# MCU.net
KiCad netlist of a schematic drawn in Altium Designer
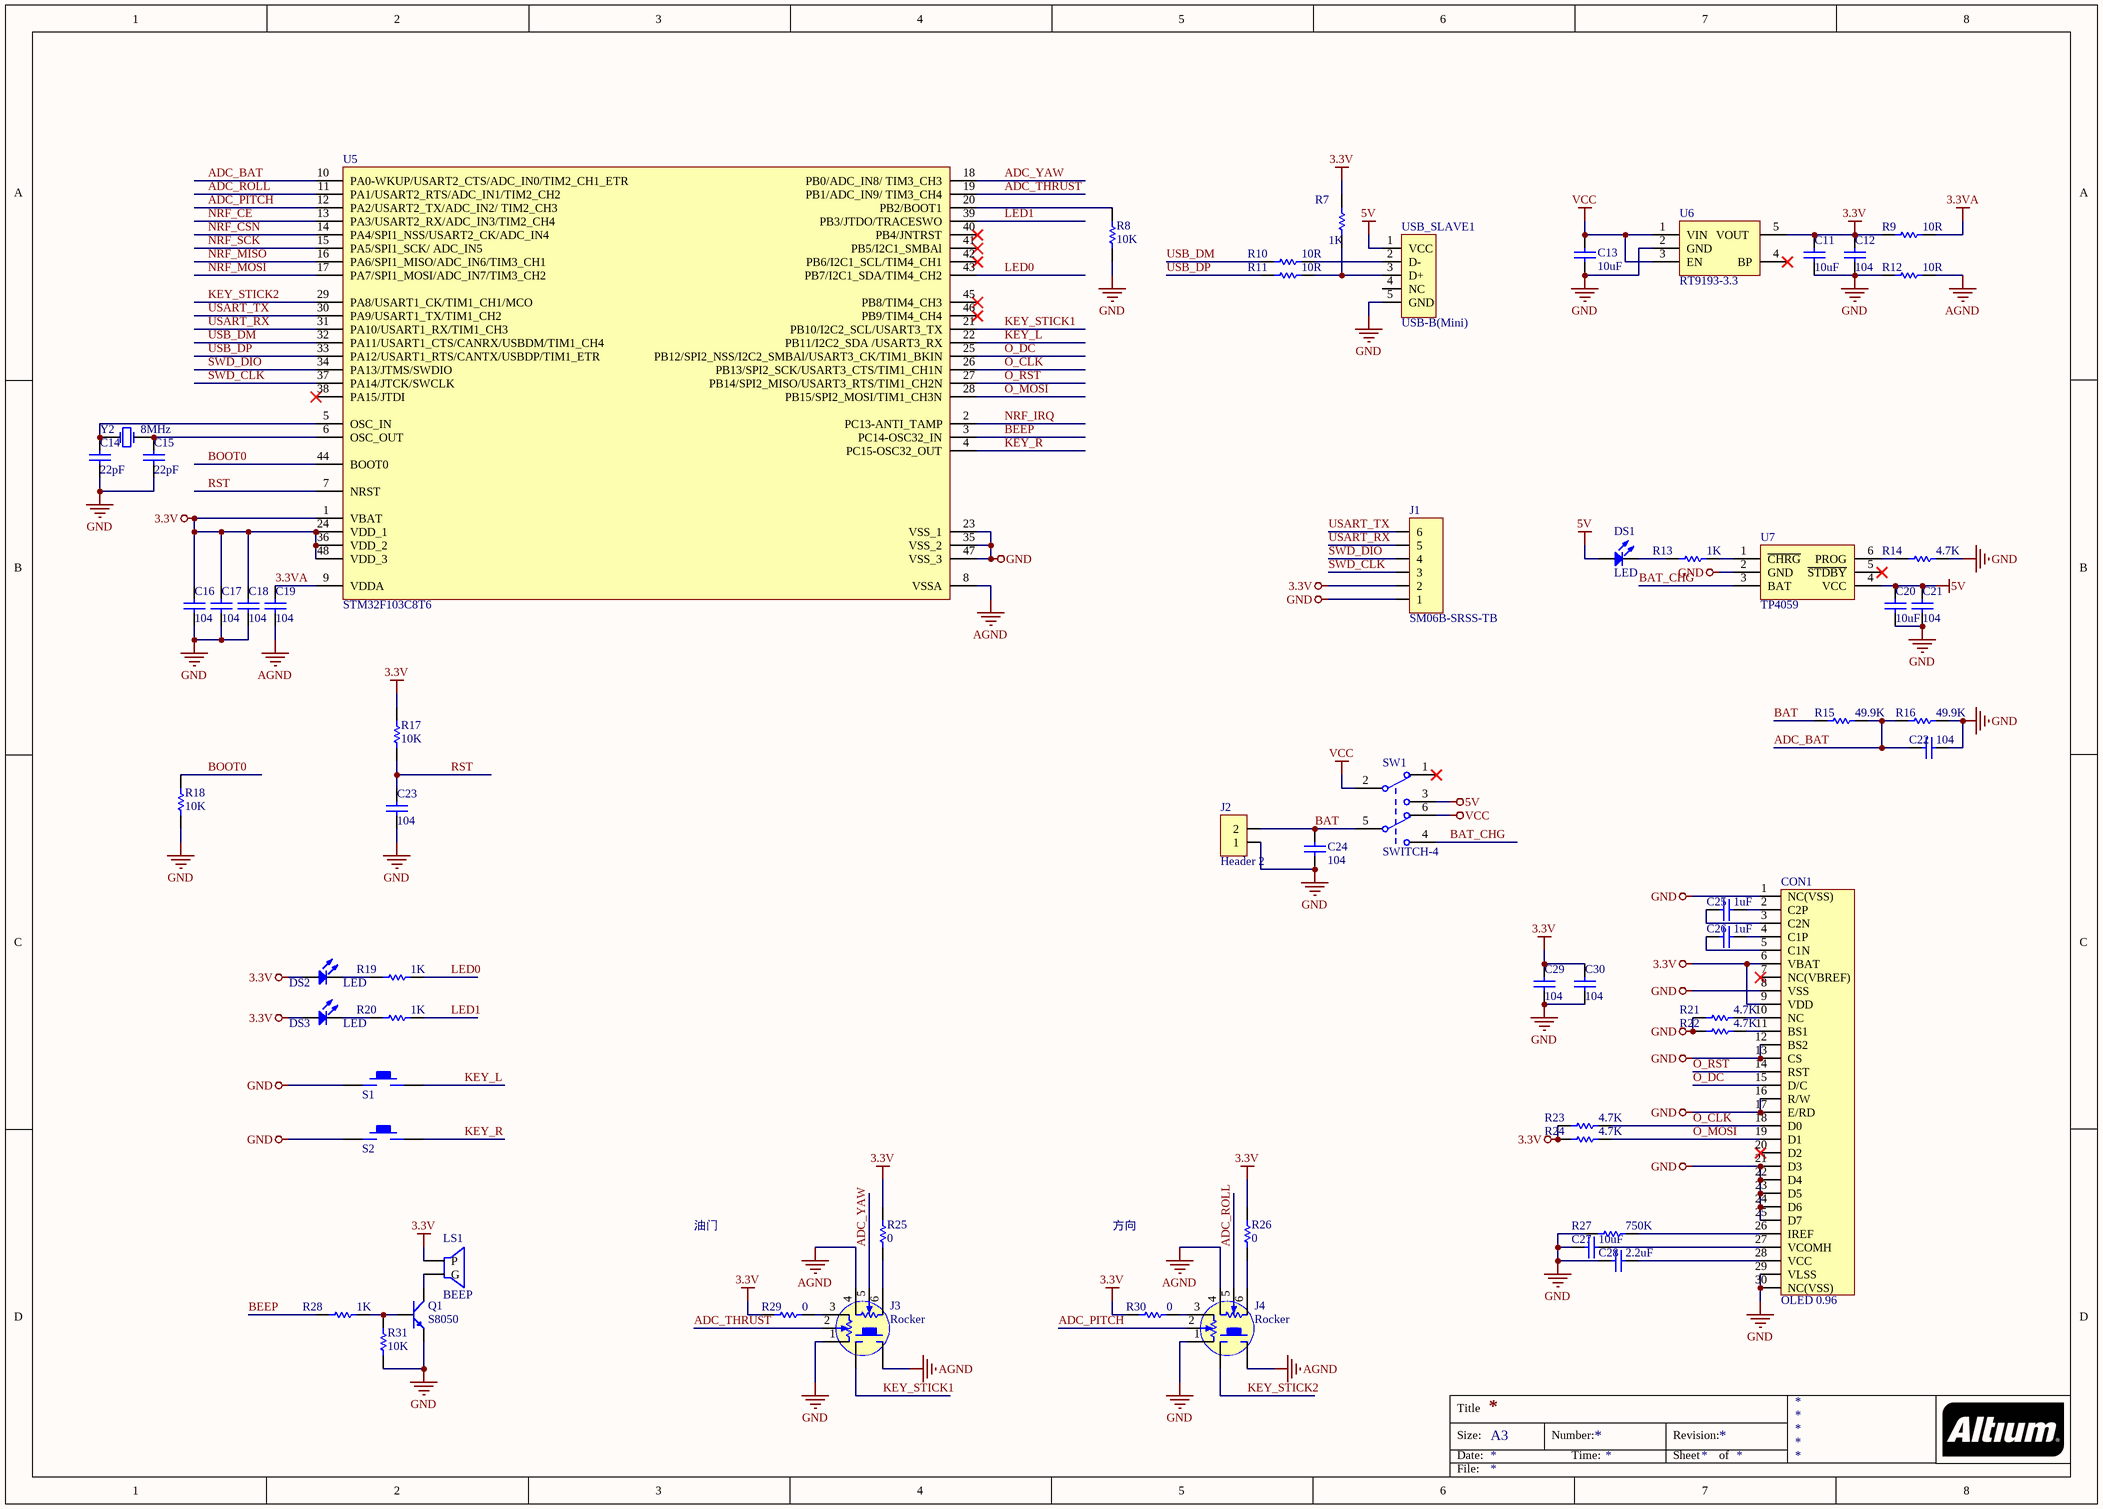
[diagram p0: MCU.SchDoc]

(export (version "E")
  (design (tool "Eeschema 10.0.6"))
  (components
    (comp (ref "C11")
      (value "10uF")
      (footprint "C0603")
      (description "电容")
      (fields (field (name "PUBLISHER") "Altium Limited"))
      (libsource (lib "Devices") (part "C0603"))
    )
    (comp (ref "C12")
      (value "104")
      (footprint "C0603")
      (description "电容")
      (fields (field (name "PUBLISHER") "Altium Limited"))
      (libsource (lib "Devices") (part "C0603"))
    )
    (comp (ref "C13")
      (value "10uF")
      (footprint "C0603")
      (description "电容")
      (fields (field (name "PUBLISHER") "Altium Limited"))
      (libsource (lib "Devices") (part "C0603"))
    )
    (comp (ref "C14")
      (value "22pF")
      (footprint "C0603")
      (description "电容")
      (fields (field (name "PUBLISHER") "Altium Limited"))
      (libsource (lib "Devices") (part "C0603"))
    )
    (comp (ref "C15")
      (value "22pF")
      (footprint "C0603")
      (description "电容")
      (fields (field (name "PUBLISHER") "Altium Limited"))
      (libsource (lib "Devices") (part "C0603"))
    )
    (comp (ref "C16")
      (value "104")
      (footprint "C0603")
      (description "电容")
      (fields (field (name "PUBLISHER") "Altium Limited"))
      (libsource (lib "Devices") (part "C0603"))
    )
    (comp (ref "C17")
      (value "104")
      (footprint "C0603")
      (description "电容")
      (fields (field (name "PUBLISHER") "Altium Limited"))
      (libsource (lib "Devices") (part "C0603"))
    )
    (comp (ref "C18")
      (value "104")
      (footprint "C0603")
      (description "电容")
      (fields (field (name "PUBLISHER") "Altium Limited"))
      (libsource (lib "Devices") (part "C0603"))
    )
    (comp (ref "C19")
      (value "104")
      (footprint "C0603")
      (description "电容")
      (fields (field (name "PUBLISHER") "Altium Limited"))
      (libsource (lib "Devices") (part "C0603"))
    )
    (comp (ref "C20")
      (value "10uF")
      (footprint "C0603")
      (description "电容")
      (fields (field (name "PUBLISHER") "Altium Limited"))
      (libsource (lib "Devices") (part "C0603"))
    )
    (comp (ref "C21")
      (value "104")
      (footprint "C0603")
      (description "电容")
      (fields (field (name "PUBLISHER") "Altium Limited"))
      (libsource (lib "Devices") (part "C0603"))
    )
    (comp (ref "C22")
      (value "104")
      (footprint "C0603")
      (description "电容")
      (fields (field (name "PUBLISHER") "Altium Limited"))
      (libsource (lib "Devices") (part "C0603"))
    )
    (comp (ref "C23")
      (value "104")
      (footprint "C0603")
      (description "电容")
      (fields (field (name "PUBLISHER") "Altium Limited"))
      (libsource (lib "Devices") (part "C0603"))
    )
    (comp (ref "C24")
      (value "104")
      (footprint "C0603")
      (description "电容")
      (fields (field (name "PUBLISHER") "Altium Limited"))
      (libsource (lib "Devices") (part "C0603"))
    )
    (comp (ref "C25")
      (value "1uF")
      (footprint "C0603")
      (description "电容")
      (fields (field (name "PUBLISHER") "Altium Limited"))
      (libsource (lib "Devices") (part "C0603"))
    )
    (comp (ref "C26")
      (value "1uF")
      (footprint "C0603")
      (description "电容")
      (fields (field (name "PUBLISHER") "Altium Limited"))
      (libsource (lib "Devices") (part "C0603"))
    )
    (comp (ref "C27")
      (value "10uF")
      (footprint "C0603")
      (description "电容")
      (fields (field (name "PUBLISHER") "Altium Limited"))
      (libsource (lib "Devices") (part "C0603"))
    )
    (comp (ref "C28")
      (value "2.2uF")
      (footprint "C0603")
      (description "电容")
      (fields (field (name "PUBLISHER") "Altium Limited"))
      (libsource (lib "Devices") (part "C0603"))
    )
    (comp (ref "C29")
      (value "104")
      (footprint "C0603")
      (description "电容")
      (fields (field (name "PUBLISHER") "Altium Limited"))
      (libsource (lib "Devices") (part "C0603"))
    )
    (comp (ref "C30")
      (value "104")
      (footprint "C0603")
      (description "电容")
      (fields (field (name "PUBLISHER") "Altium Limited"))
      (libsource (lib "Devices") (part "C0603"))
    )
    (comp (ref "CON1")
      (value "OLED 0.96")
      (footprint "OLED_0.96-L")
      (libsource (lib "Devices") (part "OLED 0.96"))
    )
    (comp (ref "DS1")
      (value "LED")
      (footprint "LED0603")
      (description "Typical RED, GREEN, YELLOW, AMBER GaAs LED")
      (fields (field (name "PUBLISHER") "Altium Limited"))
      (libsource (lib "Devices") (part "LED"))
    )
    (comp (ref "DS2")
      (value "LED")
      (footprint "LED0603")
      (description "Typical RED, GREEN, YELLOW, AMBER GaAs LED")
      (fields (field (name "PUBLISHER") "Altium Limited"))
      (libsource (lib "Devices") (part "LED"))
    )
    (comp (ref "DS3")
      (value "LED")
      (footprint "LED0603")
      (description "Typical RED, GREEN, YELLOW, AMBER GaAs LED")
      (fields (field (name "PUBLISHER") "Altium Limited"))
      (libsource (lib "Devices") (part "LED"))
    )
    (comp (ref "J1")
      (value "SM06B-SRSS-TB")
      (footprint "SM06B-SRSS-TB")
      (libsource (lib "Connectors") (part "SM06B-SRSS-TB"))
    )
    (comp (ref "J2")
      (value "Header 2")
      (footprint "HDR1X2-2MM")
      (description "Header, 2-Pin")
      (fields (field (name "PUBLISHER") "Altium Limited"))
      (libsource (lib "Connectors") (part "Header 2"))
    )
    (comp (ref "J3")
      (value "Rocker")
      (footprint "Rocker-RKJXV1224005")
      (description "航模摇杆")
      (libsource (lib "Devices") (part "Rocker"))
    )
    (comp (ref "J4")
      (value "Rocker")
      (footprint "Rocker-RKJXV1224005")
      (description "航模摇杆")
      (libsource (lib "Devices") (part "Rocker"))
    )
    (comp (ref "LS1")
      (value "BEEP")
      (footprint "BEEP-9")
      (description "蜂鸣器")
      (libsource (lib "Devices") (part "BEEP"))
    )
    (comp (ref "Q1")
      (value "S8050")
      (footprint "SOT-23R")
      (description "8050/BCW846/BCW847")
      (libsource (lib "Devices") (part "NPN"))
    )
    (comp (ref "R7")
      (value "1K")
      (footprint "R0603")
      (description "电阻")
      (fields (field (name "PUBLISHER") "Altium Limited"))
      (libsource (lib "Devices") (part "RES0603"))
    )
    (comp (ref "R8")
      (value "10K")
      (footprint "R0603")
      (description "电阻")
      (fields (field (name "PUBLISHER") "Altium Limited"))
      (libsource (lib "Devices") (part "RES0603"))
    )
    (comp (ref "R9")
      (value "10R")
      (footprint "R0603")
      (description "电阻")
      (fields (field (name "PUBLISHER") "Altium Limited"))
      (libsource (lib "Devices") (part "RES0603"))
    )
    (comp (ref "R10")
      (value "10R")
      (footprint "R0603")
      (description "电阻")
      (fields (field (name "PUBLISHER") "Altium Limited"))
      (libsource (lib "Devices") (part "RES0603"))
    )
    (comp (ref "R11")
      (value "10R")
      (footprint "R0603")
      (description "电阻")
      (fields (field (name "PUBLISHER") "Altium Limited"))
      (libsource (lib "Devices") (part "RES0603"))
    )
    (comp (ref "R12")
      (value "10R")
      (footprint "R0603")
      (description "电阻")
      (fields (field (name "PUBLISHER") "Altium Limited"))
      (libsource (lib "Devices") (part "RES0603"))
    )
    (comp (ref "R13")
      (value "1K")
      (footprint "R0603")
      (description "电阻")
      (fields (field (name "PUBLISHER") "Altium Limited"))
      (libsource (lib "Devices") (part "RES0603"))
    )
    (comp (ref "R14")
      (value "4.7K")
      (footprint "R0603")
      (description "电阻")
      (fields (field (name "PUBLISHER") "Altium Limited"))
      (libsource (lib "Devices") (part "RES0603"))
    )
    (comp (ref "R15")
      (value "49.9K")
      (footprint "R0603")
      (description "电阻")
      (fields (field (name "PUBLISHER") "Altium Limited"))
      (libsource (lib "Devices") (part "RES0603"))
    )
    (comp (ref "R16")
      (value "49.9K")
      (footprint "R0603")
      (description "电阻")
      (fields (field (name "PUBLISHER") "Altium Limited"))
      (libsource (lib "Devices") (part "RES0603"))
    )
    (comp (ref "R17")
      (value "10K")
      (footprint "R0603")
      (description "电阻")
      (fields (field (name "PUBLISHER") "Altium Limited"))
      (libsource (lib "Devices") (part "RES0603"))
    )
    (comp (ref "R18")
      (value "10K")
      (footprint "R0603")
      (description "电阻")
      (fields (field (name "PUBLISHER") "Altium Limited"))
      (libsource (lib "Devices") (part "RES0603"))
    )
    (comp (ref "R19")
      (value "1K")
      (footprint "R0603")
      (description "电阻")
      (fields (field (name "PUBLISHER") "Altium Limited"))
      (libsource (lib "Devices") (part "RES0603"))
    )
    (comp (ref "R20")
      (value "1K")
      (footprint "R0603")
      (description "电阻")
      (fields (field (name "PUBLISHER") "Altium Limited"))
      (libsource (lib "Devices") (part "RES0603"))
    )
    (comp (ref "R21")
      (value "4.7K")
      (footprint "R0603")
      (description "电阻")
      (fields (field (name "PUBLISHER") "Altium Limited"))
      (libsource (lib "Devices") (part "RES0603"))
    )
    (comp (ref "R22")
      (value "4.7K")
      (footprint "R0603")
      (description "电阻")
      (fields (field (name "PUBLISHER") "Altium Limited"))
      (libsource (lib "Devices") (part "RES0603"))
    )
    (comp (ref "R23")
      (value "4.7K")
      (footprint "R0603")
      (description "电阻")
      (fields (field (name "PUBLISHER") "Altium Limited"))
      (libsource (lib "Devices") (part "RES0603"))
    )
    (comp (ref "R24")
      (value "4.7K")
      (footprint "R0603")
      (description "电阻")
      (fields (field (name "PUBLISHER") "Altium Limited"))
      (libsource (lib "Devices") (part "RES0603"))
    )
    (comp (ref "R25")
      (value "0")
      (footprint "R0603")
      (description "电阻")
      (fields (field (name "PUBLISHER") "Altium Limited"))
      (libsource (lib "Devices") (part "RES0603"))
    )
    (comp (ref "R26")
      (value "0")
      (footprint "R0603")
      (description "电阻")
      (fields (field (name "PUBLISHER") "Altium Limited"))
      (libsource (lib "Devices") (part "RES0603"))
    )
    (comp (ref "R27")
      (value "750K")
      (footprint "R0603")
      (description "电阻")
      (fields (field (name "PUBLISHER") "Altium Limited"))
      (libsource (lib "Devices") (part "RES0603"))
    )
    (comp (ref "R28")
      (value "1K")
      (footprint "R0603")
      (description "电阻")
      (fields (field (name "PUBLISHER") "Altium Limited"))
      (libsource (lib "Devices") (part "RES0603"))
    )
    (comp (ref "R29")
      (value "0")
      (footprint "R0603")
      (description "电阻")
      (fields (field (name "PUBLISHER") "Altium Limited"))
      (libsource (lib "Devices") (part "RES0603"))
    )
    (comp (ref "R30")
      (value "0")
      (footprint "R0603")
      (description "电阻")
      (fields (field (name "PUBLISHER") "Altium Limited"))
      (libsource (lib "Devices") (part "RES0603"))
    )
    (comp (ref "R31")
      (value "10K")
      (footprint "R0603")
      (description "电阻")
      (fields (field (name "PUBLISHER") "Altium Limited"))
      (libsource (lib "Devices") (part "RES0603"))
    )
    (comp (ref "S1")
      (value "KEY")
      (footprint "KEY-3X6X3.5-C")
      (description "普通轻触按钮")
      (libsource (lib "Devices") (part "KEY"))
    )
    (comp (ref "S2")
      (value "KEY")
      (footprint "KEY-3X6X3.5-C")
      (description "普通轻触按钮")
      (libsource (lib "Devices") (part "KEY"))
    )
    (comp (ref "SW1")
      (value "SWITCH-4")
      (footprint "SW-MSS22D18G2")
      (libsource (lib "Devices") (part "SWITCH-4"))
    )
    (comp (ref "U5")
      (value "STM32F103C8T6")
      (footprint "LQFP-48")
      (libsource (lib "IC") (part "STM32F103C8T6"))
    )
    (comp (ref "U6") (value "RT9193-3.3") (footprint "SOT-23-5") (libsource (lib "IC") (part "RT9193-3.3")))
    (comp (ref "U7")
      (value "TP4059")
      (footprint "SOT23-6")
      (description "锂电池充电IC")
      (libsource (lib "IC") (part "TP4059"))
    )
    (comp (ref "USB_SLAVE1")
      (value "USB-B(Mini)")
      (footprint "USB-MicroUSB")
      (libsource (lib "Connectors") (part "USB5"))
    )
    (comp (ref "Y2")
      (value "8MHz")
      (footprint "X-NX5032GA")
      (description "Crystal Oscillator")
      (fields (field (name "PUBLISHER") "Altium Limited"))
      (libsource (lib "Devices") (part "XTAL"))
    )
  )
  (nets
    (net (code "1") (name "/ADC_BAT") (class "Default")
      (node (ref "C22") (pin "2") (pinfunction "2_2") (pintype "passive"))
      (node (ref "R15") (pin "2") (pinfunction "2_2") (pintype "passive"))
      (node (ref "R16") (pin "1") (pinfunction "1_1") (pintype "passive"))
      (node (ref "U5") (pin "10") (pinfunction "PA0-WKUP/USART2_CTS/ADC_IN0/TIM2_CH1_ETR_10") (pintype "passive"))
    )
    (net (code "2") (name "/ADC_PITCH") (class "Default")
      (node (ref "J4") (pin "2") (pinfunction "2_2") (pintype "passive"))
      (node (ref "U5") (pin "12") (pinfunction "PA2/USART2_TX/ADC_IN2/_TIM2_CH3_12") (pintype "passive"))
    )
    (net (code "3") (name "/ADC_ROLL") (class "Default")
      (node (ref "J4") (pin "5") (pinfunction "5_5") (pintype "passive"))
      (node (ref "U5") (pin "11") (pinfunction "PA1/USART2_RTS/ADC_IN1/TIM2_CH2_11") (pintype "passive"))
    )
    (net (code "4") (name "/ADC_THRUST") (class "Default")
      (node (ref "J3") (pin "2") (pinfunction "2_2") (pintype "passive"))
      (node (ref "U5") (pin "19") (pinfunction "PB1/ADC_IN9/_TIM3_CH4_19") (pintype "passive"))
    )
    (net (code "5") (name "/ADC_YAW") (class "Default")
      (node (ref "J3") (pin "5") (pinfunction "5_5") (pintype "passive"))
      (node (ref "U5") (pin "18") (pinfunction "PB0/ADC_IN8/_TIM3_CH3_18") (pintype "passive"))
    )
    (net (code "6") (name "/BAT") (class "Default")
      (node (ref "C24") (pin "1") (pinfunction "1_1") (pintype "passive"))
      (node (ref "J2") (pin "2") (pinfunction "2_2") (pintype "passive"))
      (node (ref "R15") (pin "1") (pinfunction "1_1") (pintype "passive"))
      (node (ref "SW1") (pin "5") (pinfunction "5_5") (pintype "passive"))
    )
    (net (code "7") (name "/BAT_CHG") (class "Default")
      (node (ref "SW1") (pin "4") (pinfunction "4_4") (pintype "passive"))
      (node (ref "U7") (pin "3") (pinfunction "BAT_3") (pintype "passive"))
    )
    (net (code "8") (name "/BEEP") (class "Default")
      (node (ref "R28") (pin "1") (pinfunction "1_1") (pintype "passive"))
      (node (ref "U5") (pin "3") (pinfunction "PC14-OSC32_IN_3") (pintype "passive"))
    )
    (net (code "9") (name "/BOOT0") (class "Default")
      (node (ref "R18") (pin "2") (pinfunction "2_2") (pintype "passive"))
      (node (ref "U5") (pin "44") (pinfunction "BOOT0_44") (pintype "passive"))
    )
    (net (code "10") (name "/KEY_L") (class "Default")
      (node (ref "S1") (pin "2") (pinfunction "2_2") (pintype "passive"))
      (node (ref "U5") (pin "22") (pinfunction "PB11/I2C2_SDA_/USART3_RX_22") (pintype "passive"))
    )
    (net (code "11") (name "/KEY_R") (class "Default")
      (node (ref "S2") (pin "2") (pinfunction "2_2") (pintype "passive"))
      (node (ref "U5") (pin "4") (pinfunction "PC15-OSC32_OUT_4") (pintype "passive"))
    )
    (net (code "12") (name "/KEY_STICK1") (class "Default")
      (node (ref "J3") (pin "J2") (pinfunction "J2_J2") (pintype "passive"))
      (node (ref "U5") (pin "21") (pinfunction "PB10/I2C2_SCL/USART3_TX_21") (pintype "passive"))
    )
    (net (code "13") (name "/KEY_STICK2") (class "Default")
      (node (ref "J4") (pin "J2") (pinfunction "J2_J2") (pintype "passive"))
      (node (ref "U5") (pin "29") (pinfunction "PA8/USART1_CK/TIM1_CH1/MCO_29") (pintype "passive"))
    )
    (net (code "14") (name "/LED0") (class "Default")
      (node (ref "R19") (pin "2") (pinfunction "2_2") (pintype "passive"))
      (node (ref "U5") (pin "43") (pinfunction "PB7/I2C1_SDA/TIM4_CH2_43") (pintype "passive"))
    )
    (net (code "15") (name "/LED1") (class "Default")
      (node (ref "R20") (pin "2") (pinfunction "2_2") (pintype "passive"))
      (node (ref "U5") (pin "39") (pinfunction "PB3/JTDO/TRACESWO_39") (pintype "passive"))
    )
    (net (code "16") (name "/NRF_CE") (class "Default")
      (node (ref "U5") (pin "13") (pinfunction "PA3/USART2_RX/ADC_IN3/TIM2_CH4_13") (pintype "passive"))
    )
    (net (code "17") (name "/NRF_CSN") (class "Default")
      (node (ref "U5") (pin "14") (pinfunction "PA4/SPI1_NSS/USART2_CK/ADC_IN4_14") (pintype "passive"))
    )
    (net (code "18") (name "/NRF_IRQ") (class "Default")
      (node (ref "U5") (pin "2") (pinfunction "PC13-ANTI_TAMP_2") (pintype "passive"))
    )
    (net (code "19") (name "/NRF_MISO") (class "Default")
      (node (ref "U5") (pin "16") (pinfunction "PA6/SPI1_MISO/ADC_IN6/TIM3_CH1_16") (pintype "passive"))
    )
    (net (code "20") (name "/NRF_MOSI") (class "Default")
      (node (ref "U5") (pin "17") (pinfunction "PA7/SPI1_MOSI/ADC_IN7/TIM3_CH2_17") (pintype "passive"))
    )
    (net (code "21") (name "/NRF_SCK") (class "Default")
      (node (ref "U5") (pin "15") (pinfunction "PA5/SPI1_SCK/_ADC_IN5_15") (pintype "passive"))
    )
    (net (code "22") (name "/O_CLK") (class "Default")
      (node (ref "CON1") (pin "18") (pinfunction "D0_18") (pintype "passive"))
      (node (ref "R23") (pin "2") (pinfunction "2_2") (pintype "passive"))
      (node (ref "U5") (pin "26") (pinfunction "PB13/SPI2_SCK/USART3_CTS/TIM1_CH1N_26") (pintype "passive"))
    )
    (net (code "23") (name "/O_DC") (class "Default")
      (node (ref "CON1") (pin "15") (pinfunction "D/C_15") (pintype "passive"))
      (node (ref "U5") (pin "25") (pinfunction "PB12/SPI2_NSS/I2C2_SMBAl/USART3_CK/TIM1_BKIN_25") (pintype "passive"))
    )
    (net (code "24") (name "/O_MOSI") (class "Default")
      (node (ref "CON1") (pin "19") (pinfunction "D1_19") (pintype "passive"))
      (node (ref "R24") (pin "2") (pinfunction "2_2") (pintype "passive"))
      (node (ref "U5") (pin "28") (pinfunction "PB15/SPI2_MOSI/TIM1_CH3N_28") (pintype "passive"))
    )
    (net (code "25") (name "/O_RST") (class "Default")
      (node (ref "CON1") (pin "14") (pinfunction "RST_14") (pintype "passive"))
      (node (ref "U5") (pin "27") (pinfunction "PB14/SPI2_MISO/USART3_RTS/TIM1_CH2N_27") (pintype "passive"))
    )
    (net (code "26") (name "/RST") (class "Default")
      (node (ref "C23") (pin "2") (pinfunction "2_2") (pintype "passive"))
      (node (ref "R17") (pin "1") (pinfunction "1_1") (pintype "passive"))
      (node (ref "U5") (pin "7") (pinfunction "NRST_7") (pintype "passive"))
    )
    (net (code "27") (name "/SWD_CLK") (class "Default")
      (node (ref "J1") (pin "3") (pinfunction "3_3") (pintype "passive"))
      (node (ref "U5") (pin "37") (pinfunction "PA14/JTCK/SWCLK_37") (pintype "passive"))
    )
    (net (code "28") (name "/SWD_DIO") (class "Default")
      (node (ref "J1") (pin "4") (pinfunction "4_4") (pintype "passive"))
      (node (ref "U5") (pin "34") (pinfunction "PA13/JTMS/SWDIO_34") (pintype "passive"))
    )
    (net (code "29") (name "/USART_RX") (class "Default")
      (node (ref "J1") (pin "5") (pinfunction "5_5") (pintype "passive"))
      (node (ref "U5") (pin "31") (pinfunction "PA10/USART1_RX/TIM1_CH3_31") (pintype "passive"))
    )
    (net (code "30") (name "/USART_TX") (class "Default")
      (node (ref "J1") (pin "6") (pinfunction "6_6") (pintype "passive"))
      (node (ref "U5") (pin "30") (pinfunction "PA9/USART1_TX/TIM1_CH2_30") (pintype "passive"))
    )
    (net (code "31") (name "/USB_DM") (class "Default")
      (node (ref "R10") (pin "1") (pinfunction "1_1") (pintype "passive"))
      (node (ref "U5") (pin "32") (pinfunction "PA11/USART1_CTS/CANRX/USBDM/TIM1_CH4_32") (pintype "passive"))
    )
    (net (code "32") (name "/USB_DP") (class "Default")
      (node (ref "R11") (pin "1") (pinfunction "1_1") (pintype "passive"))
      (node (ref "U5") (pin "33") (pinfunction "PA12/USART1_RTS/CANTX/USBDP/TIM1_ETR_33") (pintype "passive"))
    )
    (net (code "33") (name "3.3V") (class "Default")
      (node (ref "C11") (pin "2") (pinfunction "2_2") (pintype "passive"))
      (node (ref "C12") (pin "2") (pinfunction "2_2") (pintype "passive"))
      (node (ref "C16") (pin "2") (pinfunction "2_2") (pintype "passive"))
      (node (ref "C17") (pin "2") (pinfunction "2_2") (pintype "passive"))
      (node (ref "C18") (pin "2") (pinfunction "2_2") (pintype "passive"))
      (node (ref "C29") (pin "1") (pinfunction "1_1") (pintype "passive"))
      (node (ref "C30") (pin "1") (pinfunction "1_1") (pintype "passive"))
      (node (ref "CON1") (pin "6") (pinfunction "VBAT_6") (pintype "passive"))
      (node (ref "CON1") (pin "9") (pinfunction "VDD_9") (pintype "passive"))
      (node (ref "DS2") (pin "1") (pinfunction "A_1") (pintype "passive"))
      (node (ref "DS3") (pin "1") (pinfunction "A_1") (pintype "passive"))
      (node (ref "J1") (pin "2") (pinfunction "2_2") (pintype "passive"))
      (node (ref "LS1") (pin "1") (pinfunction "P_1") (pintype "passive"))
      (node (ref "R17") (pin "2") (pinfunction "2_2") (pintype "passive"))
      (node (ref "R23") (pin "1") (pinfunction "1_1") (pintype "passive"))
      (node (ref "R24") (pin "1") (pinfunction "1_1") (pintype "passive"))
      (node (ref "R25") (pin "2") (pinfunction "2_2") (pintype "passive"))
      (node (ref "R26") (pin "2") (pinfunction "2_2") (pintype "passive"))
      (node (ref "R29") (pin "2") (pinfunction "2_2") (pintype "passive"))
      (node (ref "R30") (pin "2") (pinfunction "2_2") (pintype "passive"))
      (node (ref "R7") (pin "2") (pinfunction "2_2") (pintype "passive"))
      (node (ref "R9") (pin "1") (pinfunction "1_1") (pintype "passive"))
      (node (ref "U5") (pin "1") (pinfunction "VBAT_1") (pintype "passive"))
      (node (ref "U5") (pin "24") (pinfunction "VDD_1_24") (pintype "passive"))
      (node (ref "U5") (pin "36") (pinfunction "VDD_2_36") (pintype "passive"))
      (node (ref "U5") (pin "48") (pinfunction "VDD_3_48") (pintype "passive"))
      (node (ref "U6") (pin "5") (pinfunction "VOUT_5") (pintype "passive"))
    )
    (net (code "34") (name "3.3VA") (class "Default")
      (node (ref "C19") (pin "2") (pinfunction "2_2") (pintype "passive"))
      (node (ref "R9") (pin "2") (pinfunction "2_2") (pintype "passive"))
      (node (ref "U5") (pin "9") (pinfunction "VDDA_9") (pintype "passive"))
    )
    (net (code "35") (name "5V") (class "Default")
      (node (ref "C20") (pin "2") (pinfunction "2_2") (pintype "passive"))
      (node (ref "C21") (pin "2") (pinfunction "2_2") (pintype "passive"))
      (node (ref "DS1") (pin "1") (pinfunction "A_1") (pintype "passive"))
      (node (ref "SW1") (pin "3") (pinfunction "3_3") (pintype "passive"))
      (node (ref "U7") (pin "4") (pinfunction "VCC_4") (pintype "passive"))
      (node (ref "USB_SLAVE1") (pin "1") (pinfunction "VCC_1") (pintype "passive"))
    )
    (net (code "36") (name "AGND") (class "Default")
      (node (ref "C19") (pin "1") (pinfunction "1_1") (pintype "passive"))
      (node (ref "J3") (pin "4") (pinfunction "4_4") (pintype "passive"))
      (node (ref "J3") (pin "J1") (pinfunction "J1_J1") (pintype "passive"))
      (node (ref "J4") (pin "4") (pinfunction "4_4") (pintype "passive"))
      (node (ref "J4") (pin "J1") (pinfunction "J1_J1") (pintype "passive"))
      (node (ref "R12") (pin "2") (pinfunction "2_2") (pintype "passive"))
      (node (ref "U5") (pin "8") (pinfunction "VSSA_8") (pintype "passive"))
    )
    (net (code "37") (name "GND") (class "Default")
      (node (ref "C11") (pin "1") (pinfunction "1_1") (pintype "passive"))
      (node (ref "C12") (pin "1") (pinfunction "1_1") (pintype "passive"))
      (node (ref "C13") (pin "1") (pinfunction "1_1") (pintype "passive"))
      (node (ref "C14") (pin "1") (pinfunction "1_1") (pintype "passive"))
      (node (ref "C15") (pin "1") (pinfunction "1_1") (pintype "passive"))
      (node (ref "C16") (pin "1") (pinfunction "1_1") (pintype "passive"))
      (node (ref "C17") (pin "1") (pinfunction "1_1") (pintype "passive"))
      (node (ref "C18") (pin "1") (pinfunction "1_1") (pintype "passive"))
      (node (ref "C20") (pin "1") (pinfunction "1_1") (pintype "passive"))
      (node (ref "C21") (pin "1") (pinfunction "1_1") (pintype "passive"))
      (node (ref "C22") (pin "1") (pinfunction "1_1") (pintype "passive"))
      (node (ref "C23") (pin "1") (pinfunction "1_1") (pintype "passive"))
      (node (ref "C24") (pin "2") (pinfunction "2_2") (pintype "passive"))
      (node (ref "C27") (pin "2") (pinfunction "2_2") (pintype "passive"))
      (node (ref "C28") (pin "2") (pinfunction "2_2") (pintype "passive"))
      (node (ref "C29") (pin "2") (pinfunction "2_2") (pintype "passive"))
      (node (ref "C30") (pin "2") (pinfunction "2_2") (pintype "passive"))
      (node (ref "CON1") (pin "1") (pinfunction "NC(VSS)_1") (pintype "passive"))
      (node (ref "CON1") (pin "12") (pinfunction "BS2_12") (pintype "passive"))
      (node (ref "CON1") (pin "13") (pinfunction "CS_13") (pintype "passive"))
      (node (ref "CON1") (pin "16") (pinfunction "R/W_16") (pintype "passive"))
      (node (ref "CON1") (pin "17") (pinfunction "E/RD_17") (pintype "passive"))
      (node (ref "CON1") (pin "21") (pinfunction "D3_21") (pintype "passive"))
      (node (ref "CON1") (pin "22") (pinfunction "D4_22") (pintype "passive"))
      (node (ref "CON1") (pin "23") (pinfunction "D5_23") (pintype "passive"))
      (node (ref "CON1") (pin "24") (pinfunction "D6_24") (pintype "passive"))
      (node (ref "CON1") (pin "25") (pinfunction "D7_25") (pintype "passive"))
      (node (ref "CON1") (pin "29") (pinfunction "VLSS_29") (pintype "passive"))
      (node (ref "CON1") (pin "30") (pinfunction "NC(VSS)_30") (pintype "passive"))
      (node (ref "CON1") (pin "8") (pinfunction "VSS_8") (pintype "passive"))
      (node (ref "J1") (pin "1") (pinfunction "1_1") (pintype "passive"))
      (node (ref "J2") (pin "1") (pinfunction "1_1") (pintype "passive"))
      (node (ref "J3") (pin "1") (pinfunction "1_1") (pintype "passive"))
      (node (ref "J4") (pin "1") (pinfunction "1_1") (pintype "passive"))
      (node (ref "Q1") (pin "1") (pinfunction "E_1") (pintype "passive"))
      (node (ref "R12") (pin "1") (pinfunction "1_1") (pintype "passive"))
      (node (ref "R14") (pin "2") (pinfunction "2_2") (pintype "passive"))
      (node (ref "R16") (pin "2") (pinfunction "2_2") (pintype "passive"))
      (node (ref "R18") (pin "1") (pinfunction "1_1") (pintype "passive"))
      (node (ref "R21") (pin "1") (pinfunction "1_1") (pintype "passive"))
      (node (ref "R22") (pin "1") (pinfunction "1_1") (pintype "passive"))
      (node (ref "R27") (pin "1") (pinfunction "1_1") (pintype "passive"))
      (node (ref "R31") (pin "1") (pinfunction "1_1") (pintype "passive"))
      (node (ref "R8") (pin "1") (pinfunction "1_1") (pintype "passive"))
      (node (ref "S1") (pin "1") (pinfunction "1_1") (pintype "passive"))
      (node (ref "S2") (pin "1") (pinfunction "1_1") (pintype "passive"))
      (node (ref "U5") (pin "23") (pinfunction "VSS_1_23") (pintype "passive"))
      (node (ref "U5") (pin "35") (pinfunction "VSS_2_35") (pintype "passive"))
      (node (ref "U5") (pin "47") (pinfunction "VSS_3_47") (pintype "passive"))
      (node (ref "U6") (pin "2") (pinfunction "GND_2") (pintype "passive"))
      (node (ref "U7") (pin "2") (pinfunction "GND_2") (pintype "passive"))
      (node (ref "USB_SLAVE1") (pin "5") (pinfunction "GND_5") (pintype "passive"))
    )
    (net (code "38") (name "Net-(CON1-BS1)") (class "Default")
      (node (ref "CON1") (pin "11") (pinfunction "BS1_11") (pintype "passive"))
      (node (ref "R22") (pin "2") (pinfunction "2_2") (pintype "passive"))
    )
    (net (code "39") (name "Net-(CON1-C1N)") (class "Default")
      (node (ref "C26") (pin "2") (pinfunction "2_2") (pintype "passive"))
      (node (ref "CON1") (pin "5") (pinfunction "C1N_5") (pintype "passive"))
    )
    (net (code "40") (name "Net-(CON1-C1P)") (class "Default")
      (node (ref "C26") (pin "1") (pinfunction "1_1") (pintype "passive"))
      (node (ref "CON1") (pin "4") (pinfunction "C1P_4") (pintype "passive"))
    )
    (net (code "41") (name "Net-(CON1-C2N)") (class "Default")
      (node (ref "C25") (pin "2") (pinfunction "2_2") (pintype "passive"))
      (node (ref "CON1") (pin "3") (pinfunction "C2N_3") (pintype "passive"))
    )
    (net (code "42") (name "Net-(CON1-C2P)") (class "Default")
      (node (ref "C25") (pin "1") (pinfunction "1_1") (pintype "passive"))
      (node (ref "CON1") (pin "2") (pinfunction "C2P_2") (pintype "passive"))
    )
    (net (code "43") (name "Net-(CON1-IREF)") (class "Default")
      (node (ref "CON1") (pin "26") (pinfunction "IREF_26") (pintype "passive"))
      (node (ref "R27") (pin "2") (pinfunction "2_2") (pintype "passive"))
    )
    (net (code "44") (name "Net-(CON1-NC)") (class "Default")
      (node (ref "CON1") (pin "10") (pinfunction "NC_10") (pintype "passive"))
      (node (ref "R21") (pin "2") (pinfunction "2_2") (pintype "passive"))
    )
    (net (code "45") (name "Net-(CON1-VCC)") (class "Default")
      (node (ref "C28") (pin "1") (pinfunction "1_1") (pintype "passive"))
      (node (ref "CON1") (pin "28") (pinfunction "VCC_28") (pintype "passive"))
    )
    (net (code "46") (name "Net-(CON1-VCOMH)") (class "Default")
      (node (ref "C27") (pin "1") (pinfunction "1_1") (pintype "passive"))
      (node (ref "CON1") (pin "27") (pinfunction "VCOMH_27") (pintype "passive"))
    )
    (net (code "47") (name "Net-(DS1-K)") (class "Default")
      (node (ref "DS1") (pin "2") (pinfunction "K_2") (pintype "passive"))
      (node (ref "R13") (pin "1") (pinfunction "1_1") (pintype "passive"))
    )
    (net (code "48") (name "Net-(DS2-K)") (class "Default")
      (node (ref "DS2") (pin "2") (pinfunction "K_2") (pintype "passive"))
      (node (ref "R19") (pin "1") (pinfunction "1_1") (pintype "passive"))
    )
    (net (code "49") (name "Net-(DS3-K)") (class "Default")
      (node (ref "DS3") (pin "2") (pinfunction "K_2") (pintype "passive"))
      (node (ref "R20") (pin "1") (pinfunction "1_1") (pintype "passive"))
    )
    (net (code "50") (name "Net-(J3-Pad3)") (class "Default")
      (node (ref "J3") (pin "3") (pinfunction "3_3") (pintype "passive"))
      (node (ref "R29") (pin "1") (pinfunction "1_1") (pintype "passive"))
    )
    (net (code "51") (name "Net-(J3-Pad6)") (class "Default")
      (node (ref "J3") (pin "6") (pinfunction "6_6") (pintype "passive"))
      (node (ref "R25") (pin "1") (pinfunction "1_1") (pintype "passive"))
    )
    (net (code "52") (name "Net-(J4-Pad3)") (class "Default")
      (node (ref "J4") (pin "3") (pinfunction "3_3") (pintype "passive"))
      (node (ref "R30") (pin "1") (pinfunction "1_1") (pintype "passive"))
    )
    (net (code "53") (name "Net-(J4-Pad6)") (class "Default")
      (node (ref "J4") (pin "6") (pinfunction "6_6") (pintype "passive"))
      (node (ref "R26") (pin "1") (pinfunction "1_1") (pintype "passive"))
    )
    (net (code "54") (name "Net-(LS1-G)") (class "Default")
      (node (ref "LS1") (pin "2") (pinfunction "G_2") (pintype "passive"))
      (node (ref "Q1") (pin "3") (pinfunction "C_3") (pintype "passive"))
    )
    (net (code "55") (name "Net-(Q1-B)") (class "Default")
      (node (ref "Q1") (pin "2") (pinfunction "B_2") (pintype "passive"))
      (node (ref "R28") (pin "2") (pinfunction "2_2") (pintype "passive"))
      (node (ref "R31") (pin "2") (pinfunction "2_2") (pintype "passive"))
    )
    (net (code "56") (name "Net-(U5-OSC_IN)") (class "Default")
      (node (ref "C14") (pin "2") (pinfunction "2_2") (pintype "passive"))
      (node (ref "U5") (pin "5") (pinfunction "OSC_IN_5") (pintype "passive"))
      (node (ref "Y2") (pin "1") (pinfunction "OSC1_1") (pintype "passive"))
    )
    (net (code "57") (name "Net-(U5-OSC_OUT)") (class "Default")
      (node (ref "C15") (pin "2") (pinfunction "2_2") (pintype "passive"))
      (node (ref "U5") (pin "6") (pinfunction "OSC_OUT_6") (pintype "passive"))
      (node (ref "Y2") (pin "2") (pinfunction "OSC2_2") (pintype "passive"))
    )
    (net (code "58") (name "Net-(U5-PB2{slash}BOOT1)") (class "Default")
      (node (ref "R8") (pin "2") (pinfunction "2_2") (pintype "passive"))
      (node (ref "U5") (pin "20") (pinfunction "PB2/BOOT1_20") (pintype "passive"))
    )
    (net (code "59") (name "Net-(U7-PROG)") (class "Default")
      (node (ref "R14") (pin "1") (pinfunction "1_1") (pintype "passive"))
      (node (ref "U7") (pin "6") (pinfunction "PROG_6") (pintype "passive"))
    )
    (net (code "60") (name "Net-(U7-~{CHRG})") (class "Default")
      (node (ref "R13") (pin "2") (pinfunction "2_2") (pintype "passive"))
      (node (ref "U7") (pin "1") (pinfunction "~{CHRG}_1") (pintype "passive"))
    )
    (net (code "61") (name "Net-(USB_SLAVE1-D+)") (class "Default")
      (node (ref "R11") (pin "2") (pinfunction "2_2") (pintype "passive"))
      (node (ref "R7") (pin "1") (pinfunction "1_1") (pintype "passive"))
      (node (ref "USB_SLAVE1") (pin "3") (pinfunction "D+_3") (pintype "passive"))
    )
    (net (code "62") (name "Net-(USB_SLAVE1-D-)") (class "Default")
      (node (ref "R10") (pin "2") (pinfunction "2_2") (pintype "passive"))
      (node (ref "USB_SLAVE1") (pin "2") (pinfunction "D-_2") (pintype "passive"))
    )
    (net (code "63") (name "VCC") (class "Default")
      (node (ref "C13") (pin "2") (pinfunction "2_2") (pintype "passive"))
      (node (ref "SW1") (pin "2") (pinfunction "2_2") (pintype "passive"))
      (node (ref "SW1") (pin "6") (pinfunction "6_6") (pintype "passive"))
      (node (ref "U6") (pin "1") (pinfunction "VIN_1") (pintype "passive"))
      (node (ref "U6") (pin "3") (pinfunction "EN_3") (pintype "passive"))
    )
    (net (code "64") (name "unconnected-(CON1-D2-Pad20)") (class "Default")
      (node (ref "CON1") (pin "20") (pinfunction "D2_20") (pintype "passive+no_connect"))
    )
    (net (code "65") (name "unconnected-(CON1-NC(VBREF)-Pad7)") (class "Default")
      (node (ref "CON1") (pin "7") (pinfunction "NC(VBREF)_7") (pintype "passive+no_connect"))
    )
    (net (code "66") (name "unconnected-(SW1-Pad1)") (class "Default")
      (node (ref "SW1") (pin "1") (pinfunction "1_1") (pintype "passive+no_connect"))
    )
    (net (code "67") (name "unconnected-(U5-PA15{slash}JTDI-Pad38)") (class "Default")
      (node (ref "U5") (pin "38") (pinfunction "PA15/JTDI_38") (pintype "passive+no_connect"))
    )
    (net (code "68") (name "unconnected-(U5-PB4{slash}JNTRST-Pad40)") (class "Default")
      (node (ref "U5") (pin "40") (pinfunction "PB4/JNTRST_40") (pintype "passive+no_connect"))
    )
    (net (code "69") (name "unconnected-(U5-PB5{slash}I2C1_SMBAl-Pad41)") (class "Default")
      (node (ref "U5") (pin "41") (pinfunction "PB5/I2C1_SMBAl_41") (pintype "passive+no_connect"))
    )
    (net (code "70") (name "unconnected-(U5-PB6{slash}I2C1_SCL{slash}TIM4_CH1-Pad42)") (class "Default")
      (node (ref "U5") (pin "42") (pinfunction "PB6/I2C1_SCL/TIM4_CH1_42") (pintype "passive+no_connect"))
    )
    (net (code "71") (name "unconnected-(U5-PB8{slash}TIM4_CH3-Pad45)") (class "Default")
      (node (ref "U5") (pin "45") (pinfunction "PB8/TIM4_CH3_45") (pintype "passive+no_connect"))
    )
    (net (code "72") (name "unconnected-(U5-PB9{slash}TIM4_CH4-Pad46)") (class "Default")
      (node (ref "U5") (pin "46") (pinfunction "PB9/TIM4_CH4_46") (pintype "passive+no_connect"))
    )
    (net (code "73") (name "unconnected-(U6-BP-Pad4)") (class "Default")
      (node (ref "U6") (pin "4") (pinfunction "BP_4") (pintype "passive+no_connect"))
    )
    (net (code "74") (name "unconnected-(U7-~{STDBY}-Pad5)") (class "Default")
      (node (ref "U7") (pin "5") (pinfunction "~{STDBY}_5") (pintype "passive+no_connect"))
    )
    (net (code "75") (name "unconnected-(USB_SLAVE1-NC-Pad4)") (class "Default")
      (node (ref "USB_SLAVE1") (pin "4") (pinfunction "NC_4") (pintype "passive"))
    )
  )
)
